# Pwm.net
KiCad netlist of a schematic drawn in EAGLE
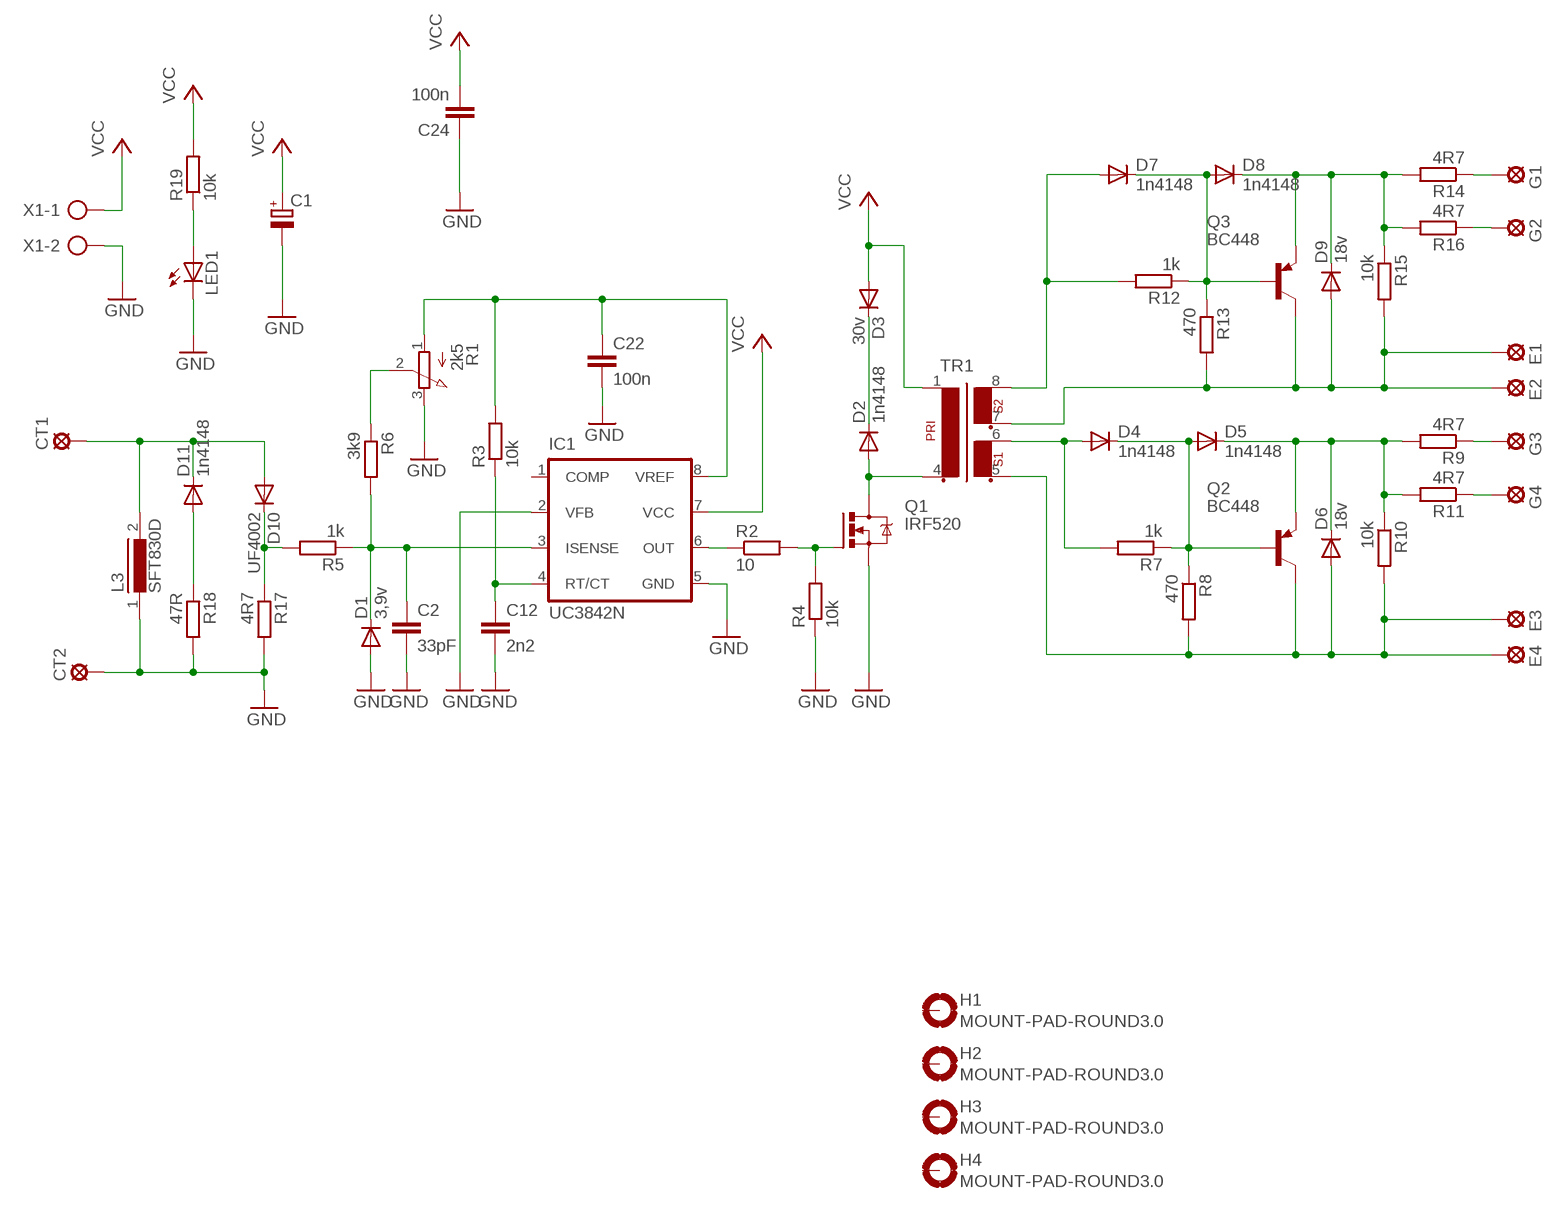
[diagram p0: schematic, sheet 1]

(export (version "E")
  (design (tool "Eeschema 10.0.6"))
  (components
    (comp (ref "C1")
      (value "CPOL-EUE5-6")
      (footprint "eagle-import:E5-6")
      (libsource (lib "eagle-import") (part "CPOL-EUE5-6"))
    )
    (comp (ref "C2")
      (value "33pF")
      (footprint "eagle-import:C050-025X075")
      (libsource (lib "eagle-import") (part "C-EU050-025X075"))
    )
    (comp (ref "C12")
      (value "2n2")
      (footprint "eagle-import:C050-025X075")
      (libsource (lib "eagle-import") (part "C-EU050-025X075"))
    )
    (comp (ref "C22")
      (value "100n")
      (footprint "eagle-import:C050-025X075")
      (libsource (lib "eagle-import") (part "C-EU050-025X075"))
    )
    (comp (ref "C24")
      (value "100n")
      (footprint "eagle-import:C050-025X075")
      (libsource (lib "eagle-import") (part "C-EU050-025X075"))
    )
    (comp (ref "CT1")
      (value "SE14")
      (footprint "eagle-import:SE14")
      (libsource (lib "eagle-import") (part "SE14"))
    )
    (comp (ref "CT2")
      (value "SE14")
      (footprint "eagle-import:SE14")
      (libsource (lib "eagle-import") (part "SE14"))
    )
    (comp (ref "D1")
      (value "3,9v")
      (footprint "eagle-import:DO35-10")
      (libsource (lib "eagle-import") (part "1N4446"))
    )
    (comp (ref "D2")
      (value "1n4148")
      (footprint "eagle-import:DO35-10")
      (libsource (lib "eagle-import") (part "1N4446"))
    )
    (comp (ref "D3")
      (value "30v")
      (footprint "eagle-import:DO35-10")
      (libsource (lib "eagle-import") (part "1N4446"))
    )
    (comp (ref "D4")
      (value "1n4148")
      (footprint "eagle-import:DO35-10")
      (libsource (lib "eagle-import") (part "1N4446"))
    )
    (comp (ref "D5")
      (value "1n4148")
      (footprint "eagle-import:DO35-10")
      (libsource (lib "eagle-import") (part "1N4446"))
    )
    (comp (ref "D6")
      (value "18v")
      (footprint "eagle-import:DO35-10")
      (libsource (lib "eagle-import") (part "1N4446"))
    )
    (comp (ref "D7")
      (value "1n4148")
      (footprint "eagle-import:DO35-10")
      (libsource (lib "eagle-import") (part "1N4446"))
    )
    (comp (ref "D8")
      (value "1n4148")
      (footprint "eagle-import:DO35-10")
      (libsource (lib "eagle-import") (part "1N4446"))
    )
    (comp (ref "D9")
      (value "18v")
      (footprint "eagle-import:DO35-10")
      (libsource (lib "eagle-import") (part "1N4446"))
    )
    (comp (ref "D10")
      (value "UF4002")
      (footprint "eagle-import:DO35-10")
      (libsource (lib "eagle-import") (part "1N4446"))
    )
    (comp (ref "D11")
      (value "1n4148")
      (footprint "eagle-import:DO35-10")
      (libsource (lib "eagle-import") (part "1N4446"))
    )
    (comp (ref "E1")
      (value "SE14")
      (footprint "eagle-import:SE14")
      (libsource (lib "eagle-import") (part "SE14"))
    )
    (comp (ref "E2")
      (value "SE14")
      (footprint "eagle-import:SE14")
      (libsource (lib "eagle-import") (part "SE14"))
    )
    (comp (ref "E3")
      (value "SE14")
      (footprint "eagle-import:SE14")
      (libsource (lib "eagle-import") (part "SE14"))
    )
    (comp (ref "E4")
      (value "SE14")
      (footprint "eagle-import:SE14")
      (libsource (lib "eagle-import") (part "SE14"))
    )
    (comp (ref "G1")
      (value "SE14")
      (footprint "eagle-import:SE14")
      (libsource (lib "eagle-import") (part "SE14"))
    )
    (comp (ref "G2")
      (value "SE14")
      (footprint "eagle-import:SE14")
      (libsource (lib "eagle-import") (part "SE14"))
    )
    (comp (ref "G3")
      (value "SE14")
      (footprint "eagle-import:SE14")
      (libsource (lib "eagle-import") (part "SE14"))
    )
    (comp (ref "G4")
      (value "SE14")
      (footprint "eagle-import:SE14")
      (libsource (lib "eagle-import") (part "SE14"))
    )
    (comp (ref "H1")
      (value "MOUNT-PAD-ROUND3.0")
      (footprint "eagle-import:3,0-PAD")
      (libsource (lib "eagle-import") (part "MOUNT-PAD-ROUND3.0"))
    )
    (comp (ref "H2")
      (value "MOUNT-PAD-ROUND3.0")
      (footprint "eagle-import:3,0-PAD")
      (libsource (lib "eagle-import") (part "MOUNT-PAD-ROUND3.0"))
    )
    (comp (ref "H3")
      (value "MOUNT-PAD-ROUND3.0")
      (footprint "eagle-import:3,0-PAD")
      (libsource (lib "eagle-import") (part "MOUNT-PAD-ROUND3.0"))
    )
    (comp (ref "H4")
      (value "MOUNT-PAD-ROUND3.0")
      (footprint "eagle-import:3,0-PAD")
      (libsource (lib "eagle-import") (part "MOUNT-PAD-ROUND3.0"))
    )
    (comp (ref "IC1")
      (value "UC3842N")
      (footprint "eagle-import:DIL08")
      (libsource (lib "eagle-import") (part "UC384N2"))
    )
    (comp (ref "L3")
      (value "SFT830D")
      (footprint "eagle-import:SFT830D")
      (libsource (lib "eagle-import") (part "SFT830D"))
    )
    (comp (ref "LED1")
      (value "LED5MM")
      (footprint "eagle-import:LED5MM")
      (libsource (lib "eagle-import") (part "LED5MM"))
    )
    (comp (ref "Q1")
      (value "IRF520")
      (footprint "eagle-import:TO220BV")
      (libsource (lib "eagle-import") (part "IRF520"))
    )
    (comp (ref "Q2")
      (value "BC448")
      (footprint "eagle-import:TO92-EBC")
      (libsource (lib "eagle-import") (part "BC448"))
    )
    (comp (ref "Q3")
      (value "BC448")
      (footprint "eagle-import:TO92-EBC")
      (libsource (lib "eagle-import") (part "BC448"))
    )
    (comp (ref "R1")
      (value "2k5")
      (footprint "eagle-import:3RP_1610N")
      (libsource (lib "eagle-import") (part "3RP/1610N"))
    )
    (comp (ref "R2")
      (value "10")
      (footprint "eagle-import:0207_10")
      (libsource (lib "eagle-import") (part "R-EU_0207/10"))
    )
    (comp (ref "R3")
      (value "10k")
      (footprint "eagle-import:0207_10")
      (libsource (lib "eagle-import") (part "R-EU_0207/10"))
    )
    (comp (ref "R4")
      (value "10k")
      (footprint "eagle-import:0207_10")
      (libsource (lib "eagle-import") (part "R-EU_0207/10"))
    )
    (comp (ref "R5")
      (value "1k")
      (footprint "eagle-import:0207_10")
      (libsource (lib "eagle-import") (part "R-EU_0207/10"))
    )
    (comp (ref "R6")
      (value "3k9")
      (footprint "eagle-import:0207_10")
      (libsource (lib "eagle-import") (part "R-EU_0207/10"))
    )
    (comp (ref "R7")
      (value "1k")
      (footprint "eagle-import:0207_10")
      (libsource (lib "eagle-import") (part "R-EU_0207/10"))
    )
    (comp (ref "R8")
      (value "470")
      (footprint "eagle-import:0207_10")
      (libsource (lib "eagle-import") (part "R-EU_0207/10"))
    )
    (comp (ref "R9")
      (value "4R7")
      (footprint "eagle-import:0207_10")
      (libsource (lib "eagle-import") (part "R-EU_0207/10"))
    )
    (comp (ref "R10")
      (value "10k")
      (footprint "eagle-import:0207_10")
      (libsource (lib "eagle-import") (part "R-EU_0207/10"))
    )
    (comp (ref "R11")
      (value "4R7")
      (footprint "eagle-import:0207_10")
      (libsource (lib "eagle-import") (part "R-EU_0207/10"))
    )
    (comp (ref "R12")
      (value "1k")
      (footprint "eagle-import:0207_10")
      (libsource (lib "eagle-import") (part "R-EU_0207/10"))
    )
    (comp (ref "R13")
      (value "470")
      (footprint "eagle-import:0207_10")
      (libsource (lib "eagle-import") (part "R-EU_0207/10"))
    )
    (comp (ref "R14")
      (value "4R7")
      (footprint "eagle-import:0207_10")
      (libsource (lib "eagle-import") (part "R-EU_0207/10"))
    )
    (comp (ref "R15")
      (value "10k")
      (footprint "eagle-import:0207_10")
      (libsource (lib "eagle-import") (part "R-EU_0207/10"))
    )
    (comp (ref "R16")
      (value "4R7")
      (footprint "eagle-import:0207_10")
      (libsource (lib "eagle-import") (part "R-EU_0207/10"))
    )
    (comp (ref "R17")
      (value "4R7")
      (footprint "eagle-import:0207_10")
      (libsource (lib "eagle-import") (part "R-EU_0207/10"))
    )
    (comp (ref "R18")
      (value "47R")
      (footprint "eagle-import:0207_10")
      (libsource (lib "eagle-import") (part "R-EU_0207/10"))
    )
    (comp (ref "R19")
      (value "10k")
      (footprint "eagle-import:0207_10")
      (libsource (lib "eagle-import") (part "R-EU_0207/10"))
    )
    (comp (ref "TR1")
      (value "EE20-2")
      (footprint "eagle-import:EE20-2")
      (libsource (lib "eagle-import") (part "EE20-2"))
    )
    (comp (ref "X1")
      (value "AK300/2")
      (footprint "eagle-import:AK300_2")
      (libsource (lib "eagle-import") (part "AK300/2"))
    )
  )
  (nets
    (net (code "1") (name "GND") (class "Default")
      (node (ref "C1") (pin "-") (pinfunction "-_-") (pintype "passive"))
      (node (ref "C12") (pin "2") (pinfunction "2_2") (pintype "passive"))
      (node (ref "C2") (pin "2") (pinfunction "2_2") (pintype "passive"))
      (node (ref "C22") (pin "2") (pinfunction "2_2") (pintype "passive"))
      (node (ref "C24") (pin "1") (pinfunction "1_1") (pintype "passive"))
      (node (ref "CT2") (pin "MP") (pinfunction "MP_MP") (pintype "passive"))
      (node (ref "D1") (pin "A") (pinfunction "A_A") (pintype "passive"))
      (node (ref "IC1") (pin "2") (pinfunction "VFB_2") (pintype "input"))
      (node (ref "IC1") (pin "5") (pinfunction "GND_5") (pintype "power_in"))
      (node (ref "L3") (pin "1") (pinfunction "1_1") (pintype "passive"))
      (node (ref "LED1") (pin "K") (pinfunction "C_K") (pintype "passive"))
      (node (ref "Q1") (pin "S") (pinfunction "S_S") (pintype "passive"))
      (node (ref "R1") (pin "3") (pinfunction "E_3") (pintype "passive"))
      (node (ref "R17") (pin "2") (pinfunction "2_2") (pintype "passive"))
      (node (ref "R18") (pin "2") (pinfunction "2_2") (pintype "passive"))
      (node (ref "R4") (pin "1") (pinfunction "1_1") (pintype "passive"))
      (node (ref "X1") (pin "2") (pinfunction "KL_2") (pintype "passive"))
    )
    (net (code "2") (name "Net-(CT1-PadMP)") (class "Default")
      (node (ref "CT1") (pin "MP") (pinfunction "MP_MP") (pintype "passive"))
      (node (ref "D10") (pin "A") (pinfunction "A_A") (pintype "passive"))
      (node (ref "D11") (pin "C") (pinfunction "C_C") (pintype "passive"))
      (node (ref "L3") (pin "2") (pinfunction "2_2") (pintype "passive"))
    )
    (net (code "3") (name "Net-(D2-PadC)") (class "Default")
      (node (ref "D2") (pin "C") (pinfunction "C_C") (pintype "passive"))
      (node (ref "D3") (pin "C") (pinfunction "C_C") (pintype "passive"))
    )
    (net (code "4") (name "Net-(D4-PadC)") (class "Default")
      (node (ref "D4") (pin "C") (pinfunction "C_C") (pintype "passive"))
      (node (ref "D5") (pin "A") (pinfunction "A_A") (pintype "passive"))
      (node (ref "Q2") (pin "B") (pinfunction "B_B") (pintype "passive"))
      (node (ref "R7") (pin "1") (pinfunction "1_1") (pintype "passive"))
      (node (ref "R8") (pin "1") (pinfunction "1_1") (pintype "passive"))
    )
    (net (code "5") (name "Net-(D5-PadC)") (class "Default")
      (node (ref "D5") (pin "C") (pinfunction "C_C") (pintype "passive"))
      (node (ref "D6") (pin "C") (pinfunction "C_C") (pintype "passive"))
      (node (ref "Q2") (pin "E") (pinfunction "E_E") (pintype "passive"))
      (node (ref "R10") (pin "1") (pinfunction "1_1") (pintype "passive"))
      (node (ref "R11") (pin "2") (pinfunction "2_2") (pintype "passive"))
      (node (ref "R9") (pin "2") (pinfunction "2_2") (pintype "passive"))
    )
    (net (code "6") (name "Net-(D7-PadC)") (class "Default")
      (node (ref "D7") (pin "C") (pinfunction "C_C") (pintype "passive"))
      (node (ref "D8") (pin "A") (pinfunction "A_A") (pintype "passive"))
      (node (ref "Q3") (pin "B") (pinfunction "B_B") (pintype "passive"))
      (node (ref "R12") (pin "1") (pinfunction "1_1") (pintype "passive"))
      (node (ref "R13") (pin "1") (pinfunction "1_1") (pintype "passive"))
    )
    (net (code "7") (name "Net-(D8-PadC)") (class "Default")
      (node (ref "D8") (pin "C") (pinfunction "C_C") (pintype "passive"))
      (node (ref "D9") (pin "C") (pinfunction "C_C") (pintype "passive"))
      (node (ref "Q3") (pin "E") (pinfunction "E_E") (pintype "passive"))
      (node (ref "R14") (pin "2") (pinfunction "2_2") (pintype "passive"))
      (node (ref "R15") (pin "1") (pinfunction "1_1") (pintype "passive"))
      (node (ref "R16") (pin "2") (pinfunction "2_2") (pintype "passive"))
    )
    (net (code "8") (name "Net-(D10-PadC)") (class "Default")
      (node (ref "D10") (pin "C") (pinfunction "C_C") (pintype "passive"))
      (node (ref "R17") (pin "1") (pinfunction "1_1") (pintype "passive"))
      (node (ref "R5") (pin "2") (pinfunction "2_2") (pintype "passive"))
    )
    (net (code "9") (name "Net-(D11-PadA)") (class "Default")
      (node (ref "D11") (pin "A") (pinfunction "A_A") (pintype "passive"))
      (node (ref "R18") (pin "1") (pinfunction "1_1") (pintype "passive"))
    )
    (net (code "10") (name "Net-(G1-PadMP)") (class "Default")
      (node (ref "G1") (pin "MP") (pinfunction "MP_MP") (pintype "passive"))
      (node (ref "R14") (pin "1") (pinfunction "1_1") (pintype "passive"))
    )
    (net (code "11") (name "Net-(G2-PadMP)") (class "Default")
      (node (ref "G2") (pin "MP") (pinfunction "MP_MP") (pintype "passive"))
      (node (ref "R16") (pin "1") (pinfunction "1_1") (pintype "passive"))
    )
    (net (code "12") (name "Net-(G3-PadMP)") (class "Default")
      (node (ref "G3") (pin "MP") (pinfunction "MP_MP") (pintype "passive"))
      (node (ref "R9") (pin "1") (pinfunction "1_1") (pintype "passive"))
    )
    (net (code "13") (name "Net-(G4-PadMP)") (class "Default")
      (node (ref "G4") (pin "MP") (pinfunction "MP_MP") (pintype "passive"))
      (node (ref "R11") (pin "1") (pinfunction "1_1") (pintype "passive"))
    )
    (net (code "14") (name "Net-(IC1-ISENSE)") (class "Default")
      (node (ref "C2") (pin "1") (pinfunction "1_1") (pintype "passive"))
      (node (ref "D1") (pin "C") (pinfunction "C_C") (pintype "passive"))
      (node (ref "IC1") (pin "3") (pinfunction "ISENSE_3") (pintype "input"))
      (node (ref "R5") (pin "1") (pinfunction "1_1") (pintype "passive"))
      (node (ref "R6") (pin "2") (pinfunction "2_2") (pintype "passive"))
    )
    (net (code "15") (name "Net-(IC1-OUT)") (class "Default")
      (node (ref "IC1") (pin "6") (pinfunction "OUT_6") (pintype "output"))
      (node (ref "R2") (pin "1") (pinfunction "1_1") (pintype "passive"))
    )
    (net (code "16") (name "Net-(IC1-RT{slash}CT)") (class "Default")
      (node (ref "C12") (pin "1") (pinfunction "1_1") (pintype "passive"))
      (node (ref "IC1") (pin "4") (pinfunction "RT/CT_4") (pintype "passive"))
      (node (ref "R3") (pin "1") (pinfunction "1_1") (pintype "passive"))
    )
    (net (code "17") (name "Net-(IC1-VREF)") (class "Default")
      (node (ref "C22") (pin "1") (pinfunction "1_1") (pintype "passive"))
      (node (ref "IC1") (pin "8") (pinfunction "VREF_8") (pintype "passive"))
      (node (ref "R1") (pin "1") (pinfunction "A_1") (pintype "passive"))
      (node (ref "R3") (pin "2") (pinfunction "2_2") (pintype "passive"))
    )
    (net (code "18") (name "Net-(LED1-PadA)") (class "Default")
      (node (ref "LED1") (pin "A") (pinfunction "A_A") (pintype "passive"))
      (node (ref "R19") (pin "1") (pinfunction "1_1") (pintype "passive"))
    )
    (net (code "19") (name "Net-(Q1-PadG)") (class "Default")
      (node (ref "Q1") (pin "G") (pinfunction "G_G") (pintype "passive"))
      (node (ref "R2") (pin "2") (pinfunction "2_2") (pintype "passive"))
      (node (ref "R4") (pin "2") (pinfunction "2_2") (pintype "passive"))
    )
    (net (code "20") (name "Net-(R1-S)") (class "Default")
      (node (ref "R1") (pin "2") (pinfunction "S_2") (pintype "passive"))
      (node (ref "R6") (pin "1") (pinfunction "1_1") (pintype "passive"))
    )
    (net (code "21") (name "Net-(TR1-2)") (class "Default")
      (node (ref "D2") (pin "A") (pinfunction "A_A") (pintype "passive"))
      (node (ref "Q1") (pin "D") (pinfunction "D_D") (pintype "passive"))
      (node (ref "TR1") (pin "4") (pinfunction "2_4") (pintype "passive"))
    )
    (net (code "22") (name "Net-(TR1-3)") (class "Default")
      (node (ref "D6") (pin "A") (pinfunction "A_A") (pintype "passive"))
      (node (ref "E3") (pin "MP") (pinfunction "MP_MP") (pintype "passive"))
      (node (ref "E4") (pin "MP") (pinfunction "MP_MP") (pintype "passive"))
      (node (ref "Q2") (pin "C") (pinfunction "C_C") (pintype "passive"))
      (node (ref "R10") (pin "2") (pinfunction "2_2") (pintype "passive"))
      (node (ref "R8") (pin "2") (pinfunction "2_2") (pintype "passive"))
      (node (ref "TR1") (pin "5") (pinfunction "3_5") (pintype "passive"))
    )
    (net (code "23") (name "Net-(TR1-4)") (class "Default")
      (node (ref "D4") (pin "A") (pinfunction "A_A") (pintype "passive"))
      (node (ref "R7") (pin "2") (pinfunction "2_2") (pintype "passive"))
      (node (ref "TR1") (pin "6") (pinfunction "4_6") (pintype "passive"))
    )
    (net (code "24") (name "Net-(TR1-5)") (class "Default")
      (node (ref "D9") (pin "A") (pinfunction "A_A") (pintype "passive"))
      (node (ref "E1") (pin "MP") (pinfunction "MP_MP") (pintype "passive"))
      (node (ref "E2") (pin "MP") (pinfunction "MP_MP") (pintype "passive"))
      (node (ref "Q3") (pin "C") (pinfunction "C_C") (pintype "passive"))
      (node (ref "R13") (pin "2") (pinfunction "2_2") (pintype "passive"))
      (node (ref "R15") (pin "2") (pinfunction "2_2") (pintype "passive"))
      (node (ref "TR1") (pin "7") (pinfunction "5_7") (pintype "passive"))
    )
    (net (code "25") (name "Net-(TR1-6)") (class "Default")
      (node (ref "D7") (pin "A") (pinfunction "A_A") (pintype "passive"))
      (node (ref "R12") (pin "2") (pinfunction "2_2") (pintype "passive"))
      (node (ref "TR1") (pin "8") (pinfunction "6_8") (pintype "passive"))
    )
    (net (code "26") (name "VCC") (class "Default")
      (node (ref "C1") (pin "+") (pinfunction "+_+") (pintype "passive"))
      (node (ref "C24") (pin "2") (pinfunction "2_2") (pintype "passive"))
      (node (ref "D3") (pin "A") (pinfunction "A_A") (pintype "passive"))
      (node (ref "IC1") (pin "7") (pinfunction "VCC_7") (pintype "power_in"))
      (node (ref "R19") (pin "2") (pinfunction "2_2") (pintype "passive"))
      (node (ref "TR1") (pin "1") (pinfunction "1_1") (pintype "passive"))
      (node (ref "X1") (pin "1") (pinfunction "KL_1") (pintype "passive"))
    )
    (net (code "27") (name "unconnected-(H1-MOUNT-PadB3,0)") (class "Default")
      (node (ref "H1") (pin "B3,0") (pinfunction "MOUNT_B3,0") (pintype "passive"))
    )
    (net (code "28") (name "unconnected-(H2-MOUNT-PadB3,0)") (class "Default")
      (node (ref "H2") (pin "B3,0") (pinfunction "MOUNT_B3,0") (pintype "passive"))
    )
    (net (code "29") (name "unconnected-(H3-MOUNT-PadB3,0)") (class "Default")
      (node (ref "H3") (pin "B3,0") (pinfunction "MOUNT_B3,0") (pintype "passive"))
    )
    (net (code "30") (name "unconnected-(H4-MOUNT-PadB3,0)") (class "Default")
      (node (ref "H4") (pin "B3,0") (pinfunction "MOUNT_B3,0") (pintype "passive"))
    )
    (net (code "31") (name "unconnected-(IC1-COMP-Pad1)") (class "Default")
      (node (ref "IC1") (pin "1") (pinfunction "COMP_1") (pintype "passive"))
    )
  )
)
